# ArcadeTouchPanel5.net
KiCad netlist of a schematic drawn in EAGLE
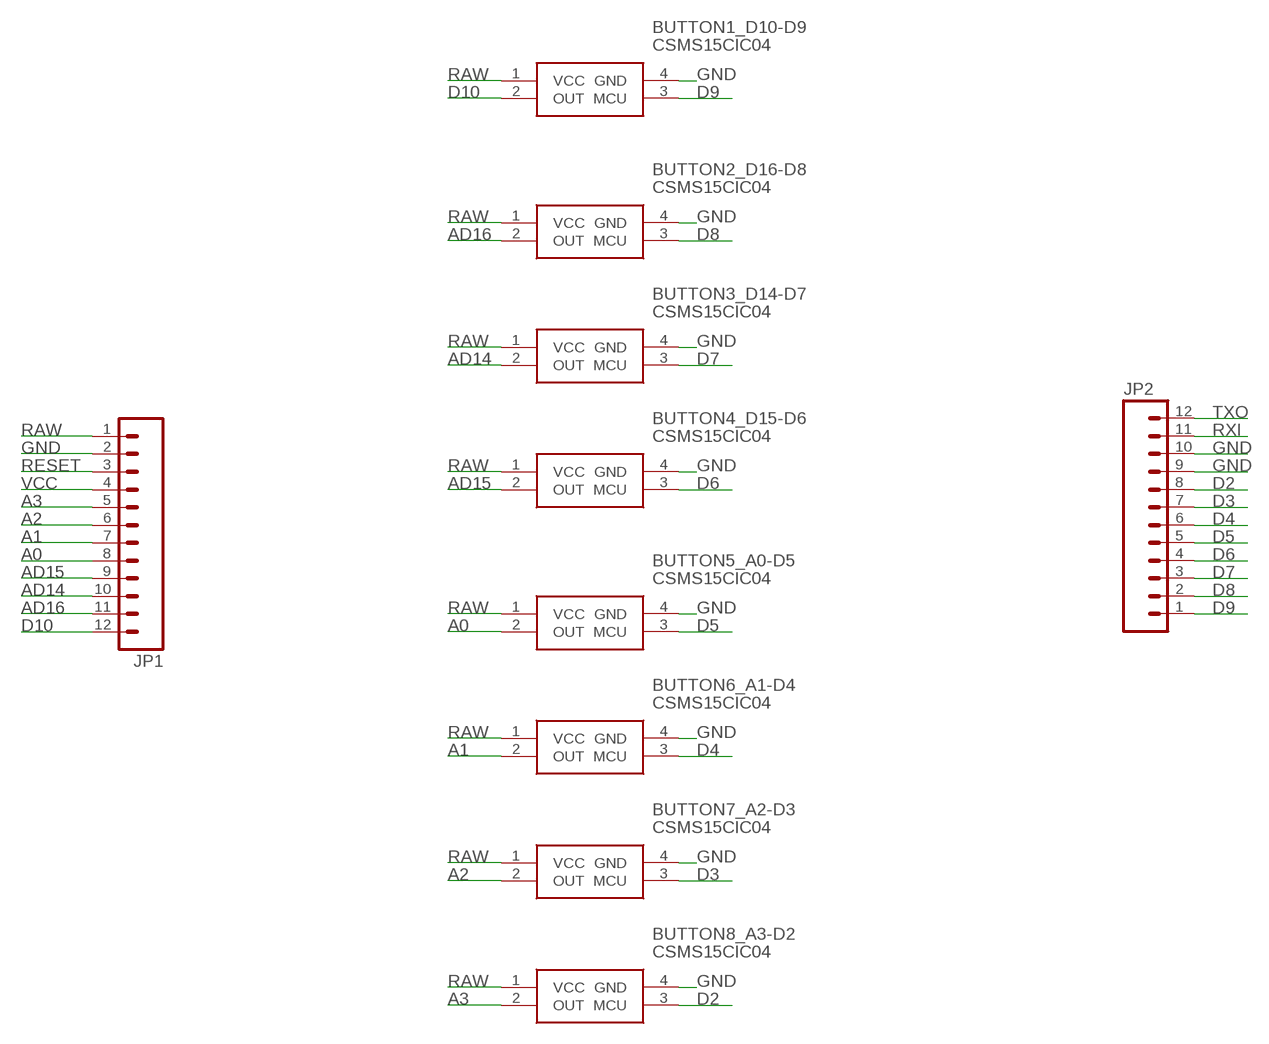
[diagram p0: schematic, sheet 1]

(export (version "E")
  (design (tool "Eeschema 10.0.6"))
  (components
    (comp (ref "BUTTON1_D10-D9")
      (value "CSMS15CIC04")
      (footprint "eagle-import:CSMS15CIC04")
      (fields (field (name "MOUSER_PART_NUMBER") "593-CSMS15CIC04"))
      (libsource (lib "eagle-import") (part "CSMS15CIC04"))
    )
    (comp (ref "BUTTON2_D16-D8")
      (value "CSMS15CIC04")
      (footprint "eagle-import:CSMS15CIC04")
      (fields (field (name "MOUSER_PART_NUMBER") "593-CSMS15CIC04"))
      (libsource (lib "eagle-import") (part "CSMS15CIC04"))
    )
    (comp (ref "BUTTON3_D14-D7")
      (value "CSMS15CIC04")
      (footprint "eagle-import:CSMS15CIC04")
      (fields (field (name "MOUSER_PART_NUMBER") "593-CSMS15CIC04"))
      (libsource (lib "eagle-import") (part "CSMS15CIC04"))
    )
    (comp (ref "BUTTON4_D15-D6")
      (value "CSMS15CIC04")
      (footprint "eagle-import:CSMS15CIC04")
      (fields (field (name "MOUSER_PART_NUMBER") "593-CSMS15CIC04"))
      (libsource (lib "eagle-import") (part "CSMS15CIC04"))
    )
    (comp (ref "BUTTON5_A0-D5")
      (value "CSMS15CIC04")
      (footprint "eagle-import:CSMS15CIC04")
      (fields (field (name "MOUSER_PART_NUMBER") "593-CSMS15CIC04"))
      (libsource (lib "eagle-import") (part "CSMS15CIC04"))
    )
    (comp (ref "BUTTON6_A1-D4")
      (value "CSMS15CIC04")
      (footprint "eagle-import:CSMS15CIC04")
      (fields (field (name "MOUSER_PART_NUMBER") "593-CSMS15CIC04"))
      (libsource (lib "eagle-import") (part "CSMS15CIC04"))
    )
    (comp (ref "BUTTON7_A2-D3")
      (value "CSMS15CIC04")
      (footprint "eagle-import:CSMS15CIC04")
      (fields (field (name "MOUSER_PART_NUMBER") "593-CSMS15CIC04"))
      (libsource (lib "eagle-import") (part "CSMS15CIC04"))
    )
    (comp (ref "BUTTON8_A3-D2")
      (value "CSMS15CIC04")
      (footprint "eagle-import:CSMS15CIC04")
      (fields (field (name "MOUSER_PART_NUMBER") "593-CSMS15CIC04"))
      (libsource (lib "eagle-import") (part "CSMS15CIC04"))
    )
    (comp (ref "JP1")
      (value "M12PTH")
      (footprint "eagle-import:1X12")
      (libsource (lib "eagle-import") (part "M12PTH"))
    )
    (comp (ref "JP2")
      (value "M12PTH")
      (footprint "eagle-import:1X12")
      (libsource (lib "eagle-import") (part "M12PTH"))
    )
  )
  (nets
    (net (code "1") (name "/A0") (class "Default")
      (node (ref "BUTTON5_A0-D5") (pin "2") (pinfunction "OUT_2") (pintype "bidirectional"))
      (node (ref "JP1") (pin "8") (pinfunction "8_8") (pintype "passive"))
    )
    (net (code "2") (name "/A1") (class "Default")
      (node (ref "BUTTON6_A1-D4") (pin "2") (pinfunction "OUT_2") (pintype "bidirectional"))
      (node (ref "JP1") (pin "7") (pinfunction "7_7") (pintype "passive"))
    )
    (net (code "3") (name "/A2") (class "Default")
      (node (ref "BUTTON7_A2-D3") (pin "2") (pinfunction "OUT_2") (pintype "bidirectional"))
      (node (ref "JP1") (pin "6") (pinfunction "6_6") (pintype "passive"))
    )
    (net (code "4") (name "/A3") (class "Default")
      (node (ref "BUTTON8_A3-D2") (pin "2") (pinfunction "OUT_2") (pintype "bidirectional"))
      (node (ref "JP1") (pin "5") (pinfunction "5_5") (pintype "passive"))
    )
    (net (code "5") (name "/AD14") (class "Default")
      (node (ref "BUTTON3_D14-D7") (pin "2") (pinfunction "OUT_2") (pintype "bidirectional"))
      (node (ref "JP1") (pin "10") (pinfunction "10_10") (pintype "passive"))
    )
    (net (code "6") (name "/AD15") (class "Default")
      (node (ref "BUTTON4_D15-D6") (pin "2") (pinfunction "OUT_2") (pintype "bidirectional"))
      (node (ref "JP1") (pin "9") (pinfunction "9_9") (pintype "passive"))
    )
    (net (code "7") (name "/AD16") (class "Default")
      (node (ref "BUTTON2_D16-D8") (pin "2") (pinfunction "OUT_2") (pintype "bidirectional"))
      (node (ref "JP1") (pin "11") (pinfunction "11_11") (pintype "passive"))
    )
    (net (code "8") (name "/D2") (class "Default")
      (node (ref "BUTTON8_A3-D2") (pin "3") (pinfunction "MCU_3") (pintype "bidirectional"))
      (node (ref "JP2") (pin "8") (pinfunction "8_8") (pintype "passive"))
    )
    (net (code "9") (name "/D3") (class "Default")
      (node (ref "BUTTON7_A2-D3") (pin "3") (pinfunction "MCU_3") (pintype "bidirectional"))
      (node (ref "JP2") (pin "7") (pinfunction "7_7") (pintype "passive"))
    )
    (net (code "10") (name "/D4") (class "Default")
      (node (ref "BUTTON6_A1-D4") (pin "3") (pinfunction "MCU_3") (pintype "bidirectional"))
      (node (ref "JP2") (pin "6") (pinfunction "6_6") (pintype "passive"))
    )
    (net (code "11") (name "/D5") (class "Default")
      (node (ref "BUTTON5_A0-D5") (pin "3") (pinfunction "MCU_3") (pintype "bidirectional"))
      (node (ref "JP2") (pin "5") (pinfunction "5_5") (pintype "passive"))
    )
    (net (code "12") (name "/D6") (class "Default")
      (node (ref "BUTTON4_D15-D6") (pin "3") (pinfunction "MCU_3") (pintype "bidirectional"))
      (node (ref "JP2") (pin "4") (pinfunction "4_4") (pintype "passive"))
    )
    (net (code "13") (name "/D7") (class "Default")
      (node (ref "BUTTON3_D14-D7") (pin "3") (pinfunction "MCU_3") (pintype "bidirectional"))
      (node (ref "JP2") (pin "3") (pinfunction "3_3") (pintype "passive"))
    )
    (net (code "14") (name "/D8") (class "Default")
      (node (ref "BUTTON2_D16-D8") (pin "3") (pinfunction "MCU_3") (pintype "bidirectional"))
      (node (ref "JP2") (pin "2") (pinfunction "2_2") (pintype "passive"))
    )
    (net (code "15") (name "/D9") (class "Default")
      (node (ref "BUTTON1_D10-D9") (pin "3") (pinfunction "MCU_3") (pintype "bidirectional"))
      (node (ref "JP2") (pin "1") (pinfunction "1_1") (pintype "passive"))
    )
    (net (code "16") (name "/D10") (class "Default")
      (node (ref "BUTTON1_D10-D9") (pin "2") (pinfunction "OUT_2") (pintype "bidirectional"))
      (node (ref "JP1") (pin "12") (pinfunction "12_12") (pintype "passive"))
    )
    (net (code "17") (name "/GND") (class "Default")
      (node (ref "BUTTON1_D10-D9") (pin "4") (pinfunction "GND_4") (pintype "bidirectional"))
      (node (ref "BUTTON2_D16-D8") (pin "4") (pinfunction "GND_4") (pintype "bidirectional"))
      (node (ref "BUTTON3_D14-D7") (pin "4") (pinfunction "GND_4") (pintype "bidirectional"))
      (node (ref "BUTTON4_D15-D6") (pin "4") (pinfunction "GND_4") (pintype "bidirectional"))
      (node (ref "BUTTON5_A0-D5") (pin "4") (pinfunction "GND_4") (pintype "bidirectional"))
      (node (ref "BUTTON6_A1-D4") (pin "4") (pinfunction "GND_4") (pintype "bidirectional"))
      (node (ref "BUTTON7_A2-D3") (pin "4") (pinfunction "GND_4") (pintype "bidirectional"))
      (node (ref "BUTTON8_A3-D2") (pin "4") (pinfunction "GND_4") (pintype "bidirectional"))
      (node (ref "JP1") (pin "2") (pinfunction "2_2") (pintype "passive"))
      (node (ref "JP2") (pin "10") (pinfunction "10_10") (pintype "passive"))
      (node (ref "JP2") (pin "9") (pinfunction "9_9") (pintype "passive"))
    )
    (net (code "18") (name "/RAW") (class "Default")
      (node (ref "BUTTON1_D10-D9") (pin "1") (pinfunction "VCC_1") (pintype "bidirectional"))
      (node (ref "BUTTON2_D16-D8") (pin "1") (pinfunction "VCC_1") (pintype "bidirectional"))
      (node (ref "BUTTON3_D14-D7") (pin "1") (pinfunction "VCC_1") (pintype "bidirectional"))
      (node (ref "BUTTON4_D15-D6") (pin "1") (pinfunction "VCC_1") (pintype "bidirectional"))
      (node (ref "BUTTON5_A0-D5") (pin "1") (pinfunction "VCC_1") (pintype "bidirectional"))
      (node (ref "BUTTON6_A1-D4") (pin "1") (pinfunction "VCC_1") (pintype "bidirectional"))
      (node (ref "BUTTON7_A2-D3") (pin "1") (pinfunction "VCC_1") (pintype "bidirectional"))
      (node (ref "BUTTON8_A3-D2") (pin "1") (pinfunction "VCC_1") (pintype "bidirectional"))
      (node (ref "JP1") (pin "1") (pinfunction "1_1") (pintype "passive"))
    )
    (net (code "19") (name "/RESET") (class "Default")
      (node (ref "JP1") (pin "3") (pinfunction "3_3") (pintype "passive"))
    )
    (net (code "20") (name "/RXI") (class "Default")
      (node (ref "JP2") (pin "11") (pinfunction "11_11") (pintype "passive"))
    )
    (net (code "21") (name "/TXO") (class "Default")
      (node (ref "JP2") (pin "12") (pinfunction "12_12") (pintype "passive"))
    )
    (net (code "22") (name "/VCC") (class "Default")
      (node (ref "JP1") (pin "4") (pinfunction "4_4") (pintype "passive"))
    )
  )
)
